# pickit4_adapter.net
KiCad netlist of a schematic drawn in EAGLE
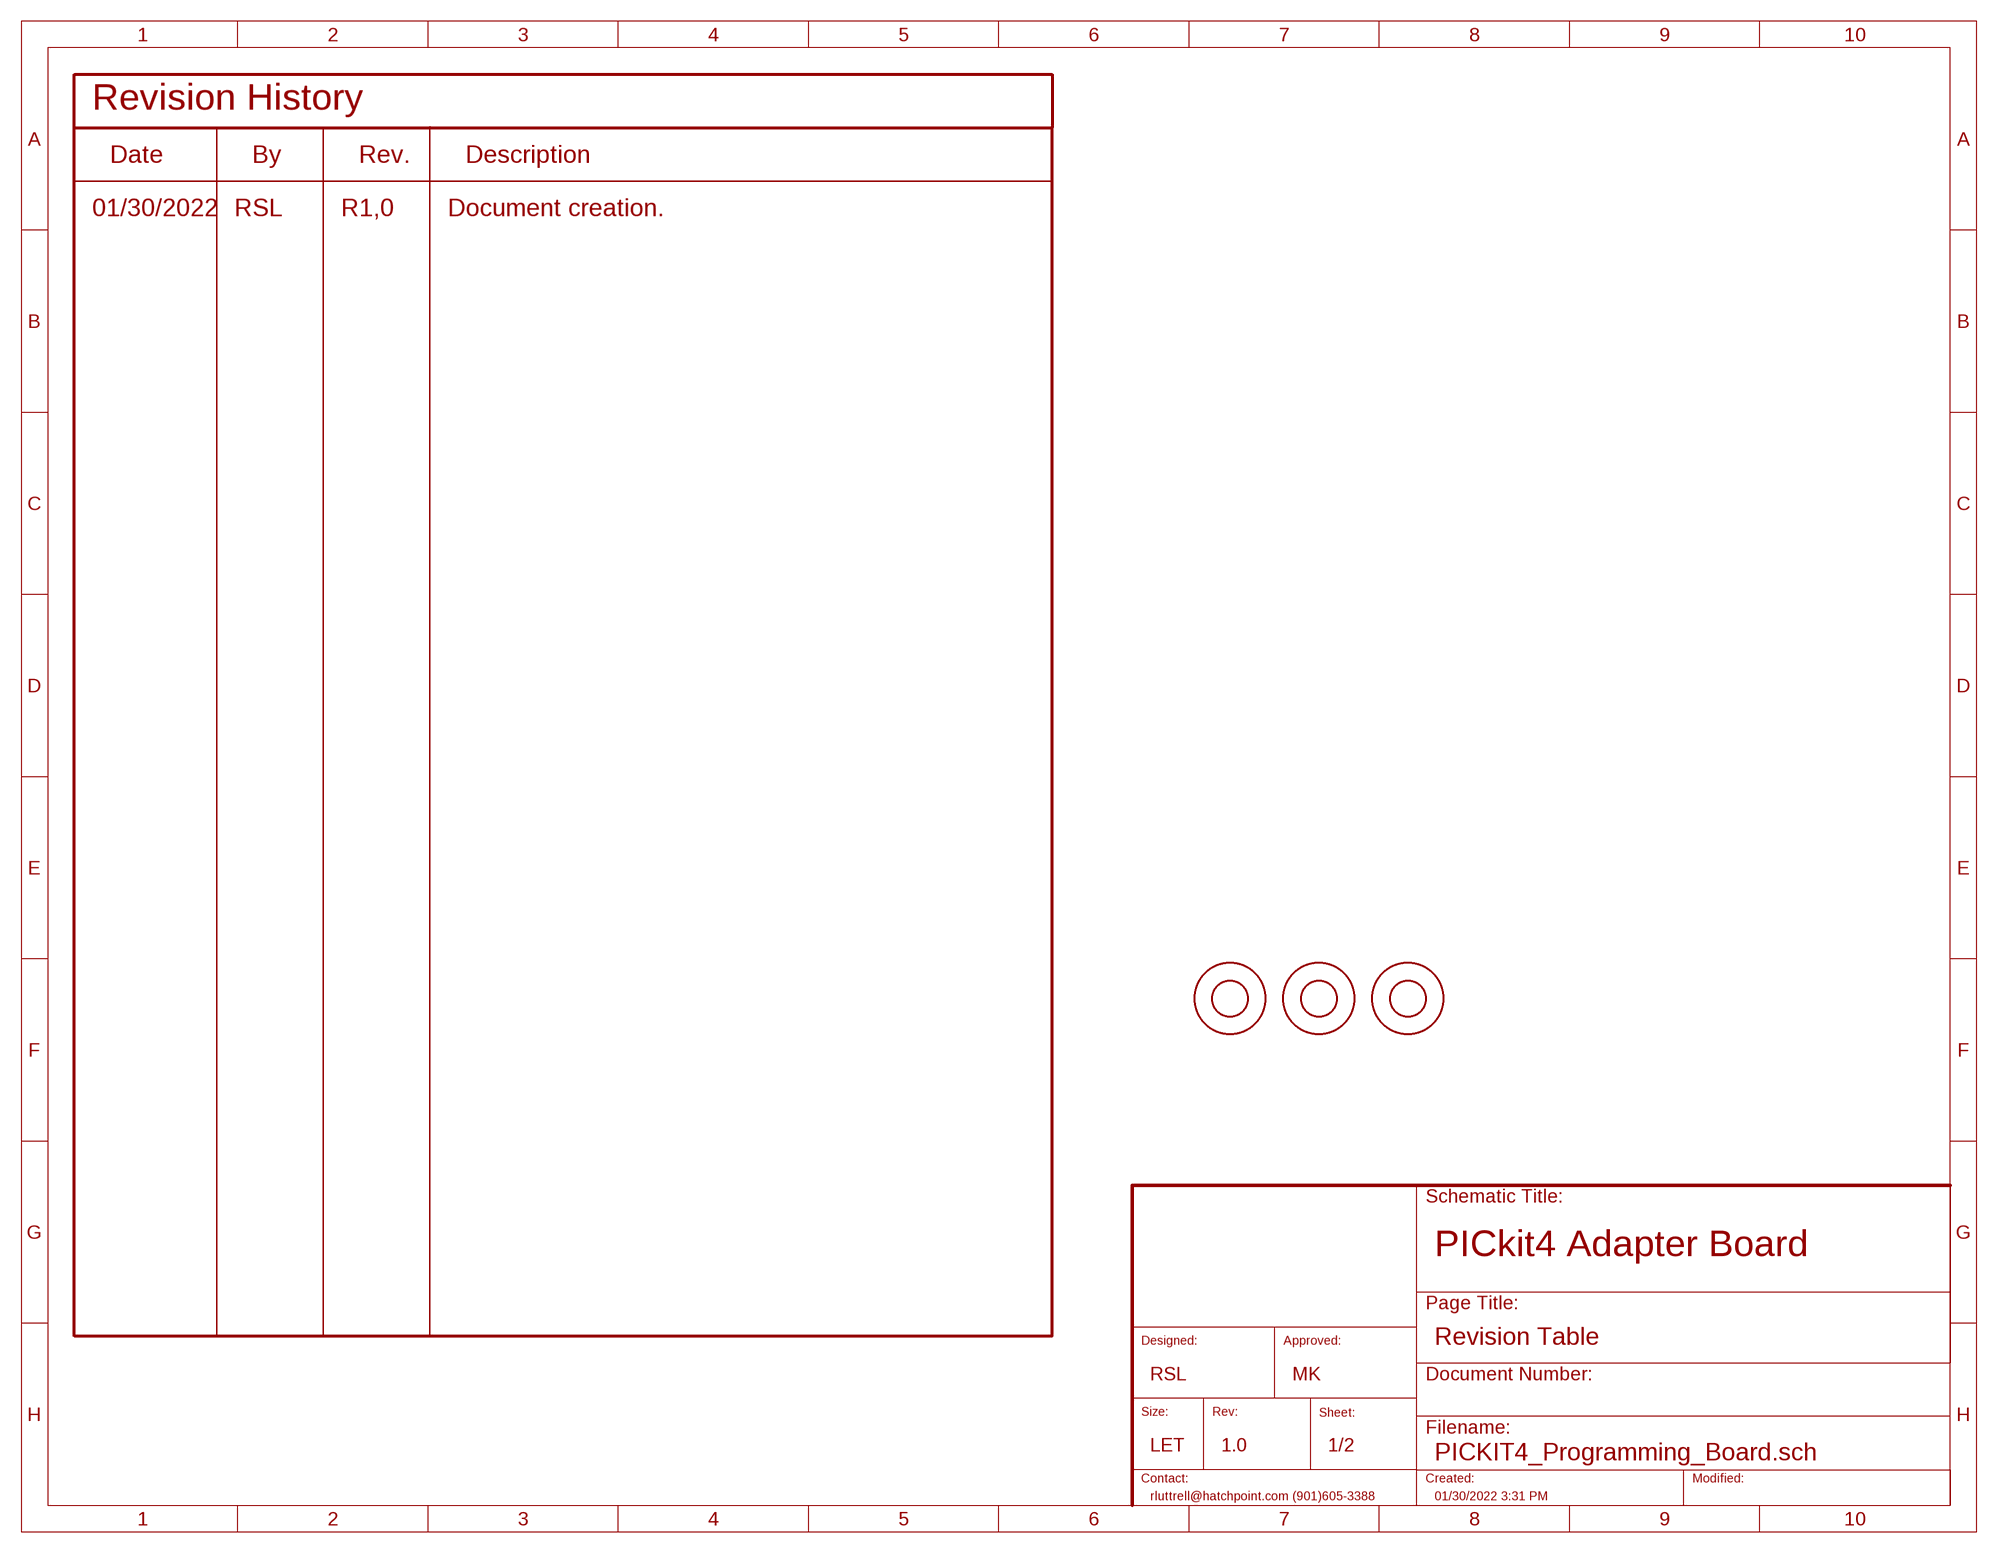
[diagram p0: schematic, sheet 1]
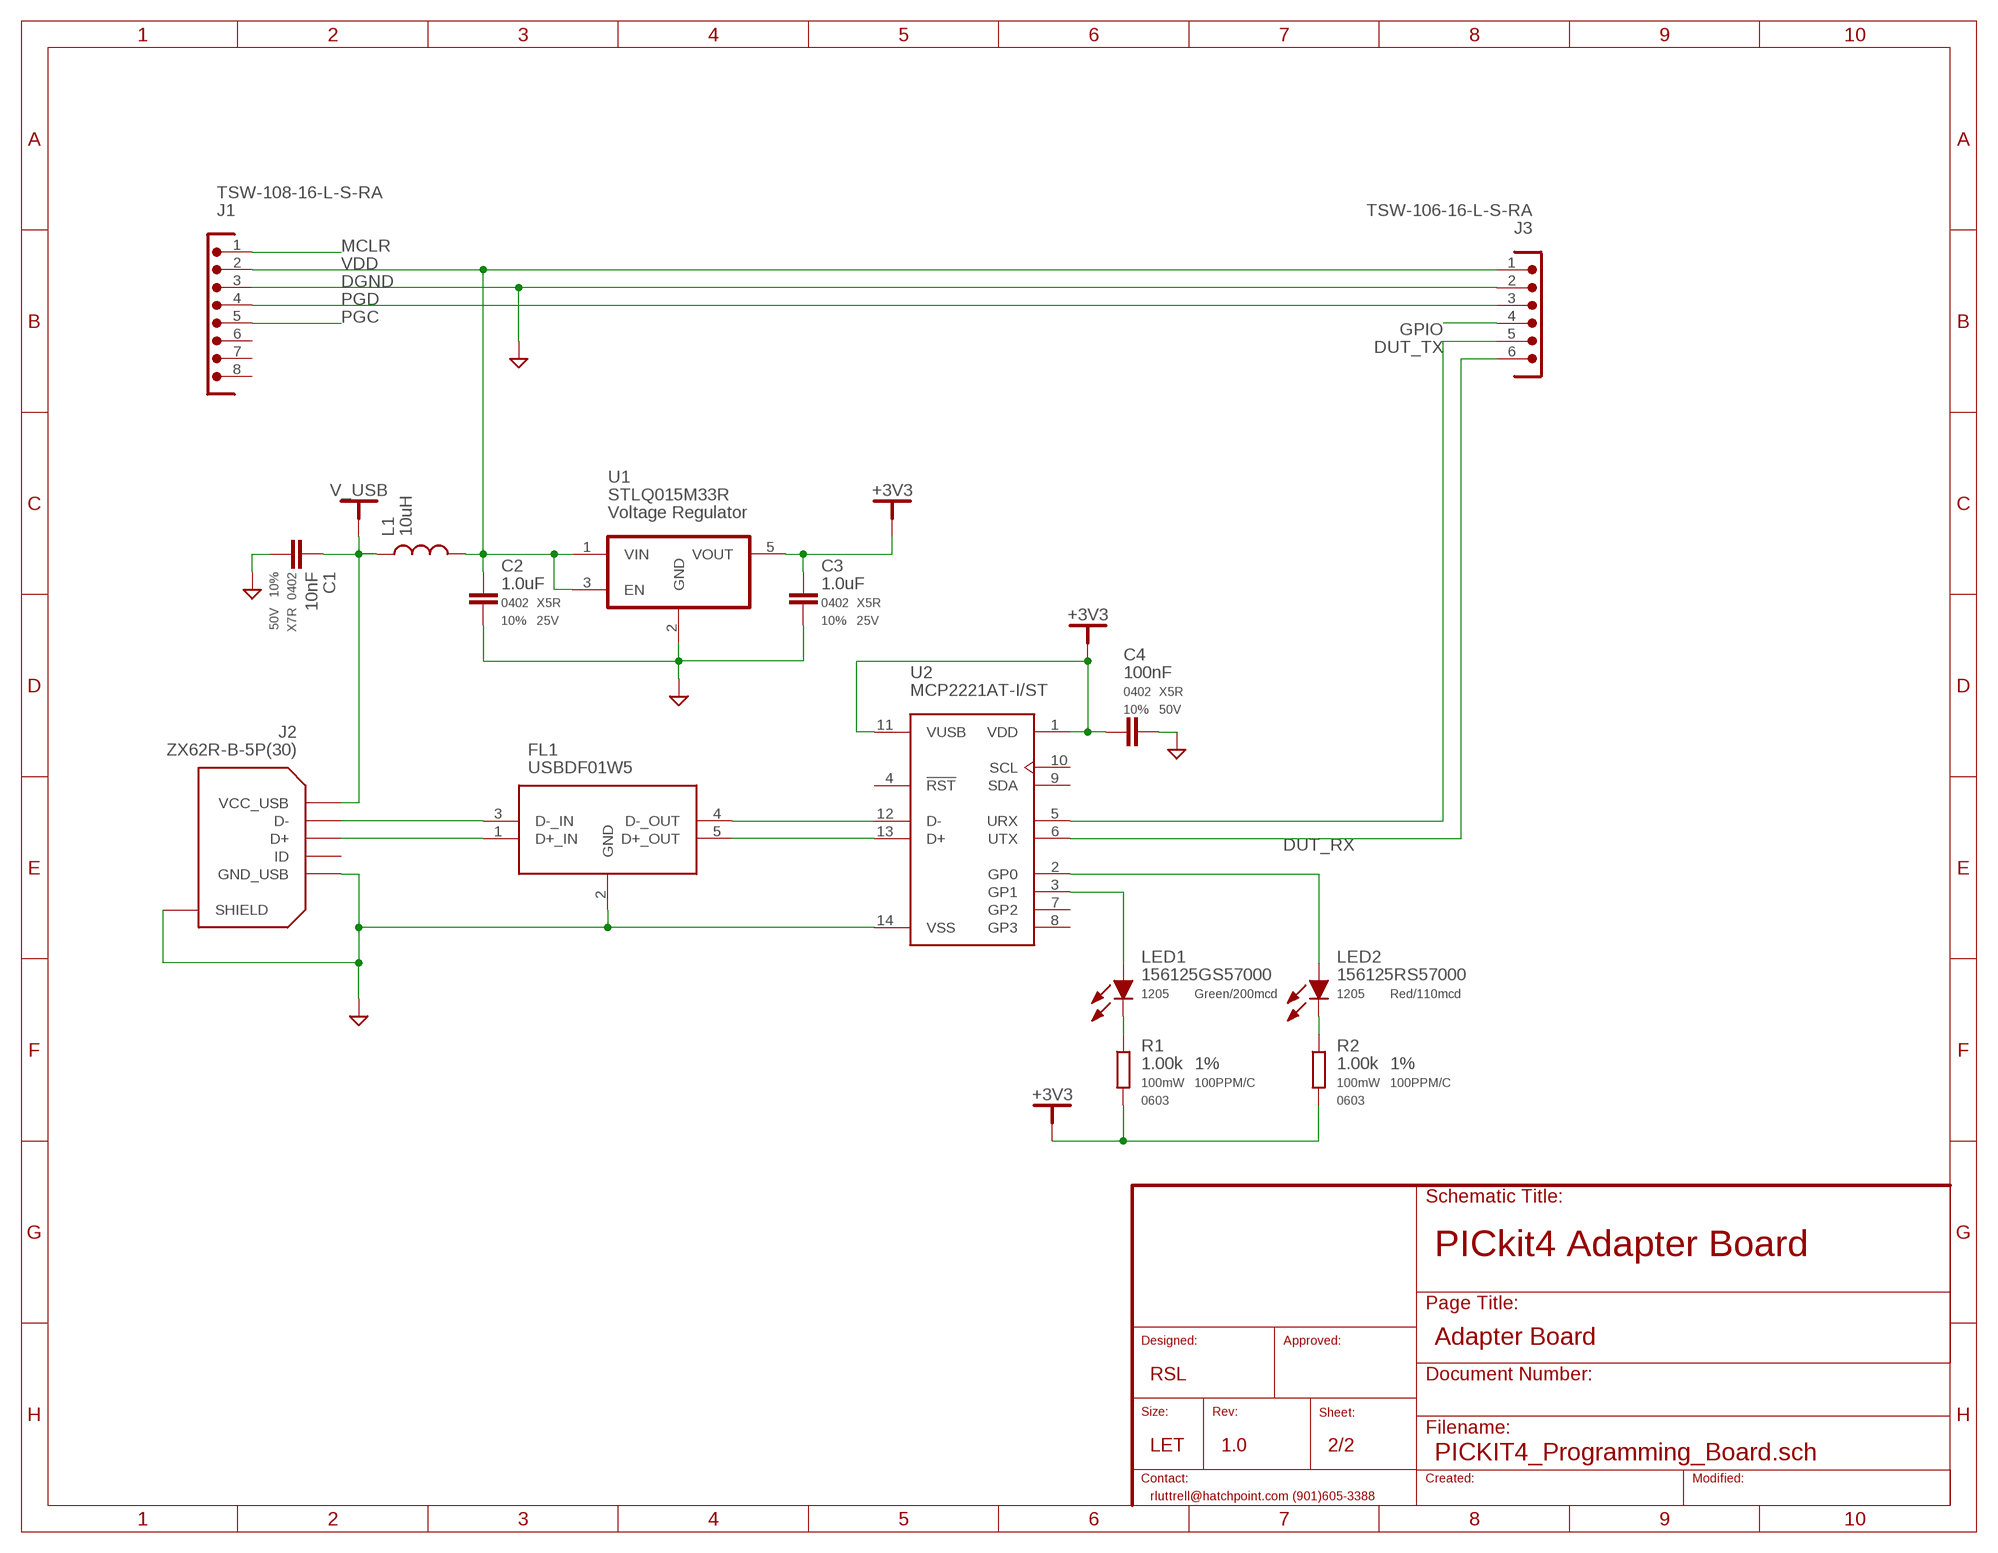
[diagram p1: schematic, sheet 2]

(export (version "E")
  (design (tool "Eeschema 10.0.6"))
  (components
    (comp (ref "C1")
      (value "10nF")
      (footprint "eagle-import:CAPC_0402_1005X55N")
      (fields
        (field (name "MANUFACTURER") "Murata")
        (field (name "PACKAGE") "0402")
        (field (name "TOL") "10%")
        (field (name "TYPE") "X7R")
        (field (name "VDC") "50V")
      )
      (libsource (lib "eagle-import") (part "GRM?155R71H103KA88D"))
    )
    (comp (ref "C2")
      (value "1.0uF")
      (footprint "eagle-import:CAPC_0402_1005X55N")
      (fields
        (field (name "MANUFACTURER") "Murata")
        (field (name "PACKAGE") "0402")
        (field (name "TOL") "10%")
        (field (name "TYPE") "X5R")
        (field (name "VDC") "25V")
      )
      (libsource (lib "eagle-import") (part "GRM?155R61E105KA12D"))
    )
    (comp (ref "C3")
      (value "1.0uF")
      (footprint "eagle-import:CAPC_0402_1005X55N")
      (fields
        (field (name "MANUFACTURER") "Murata")
        (field (name "PACKAGE") "0402")
        (field (name "TOL") "10%")
        (field (name "TYPE") "X5R")
        (field (name "VDC") "25V")
      )
      (libsource (lib "eagle-import") (part "GRM?155R61E105KA12D"))
    )
    (comp (ref "C4")
      (value "100nF")
      (footprint "eagle-import:CAPC_0402_1005X55N")
      (fields
        (field (name "MANUFACTURER") "Murata")
        (field (name "PACKAGE") "0402")
        (field (name "TOL") "10%")
        (field (name "TYPE") "X5R")
        (field (name "VDC") "50V")
      )
      (libsource (lib "eagle-import") (part "GRM?155R61H104KE19D"))
    )
    (comp (ref "FL1")
      (value "USBDF01W5")
      (footprint "eagle-import:SOT65P210X110-5N")
      (fields (field (name "MANUFACTURER") "ST"))
      (libsource (lib "eagle-import") (part "USBDF0W51"))
    )
    (comp (ref "J1")
      (value "TSW-108-16-L-S-RA")
      (footprint "eagle-import:HDR-100MIL-1X8-THRU-RA")
      (libsource (lib "eagle-import") (part "TSW-108-16-L-S-RA"))
    )
    (comp (ref "J2")
      (value "ZX62R-B-5P(30)")
      (footprint "eagle-import:ZX62R-B-5P(30)")
      (libsource (lib "eagle-import") (part "ZX62?R-B-5P(30)"))
    )
    (comp (ref "J3")
      (value "TSW-106-16-L-S-RA")
      (footprint "eagle-import:HDR-100MIL-1X6-THRU-RA")
      (libsource (lib "eagle-import") (part "TSW-106-16-L-S-RA"))
    )
    (comp (ref "L1")
      (value "10uH")
      (footprint "eagle-import:INDC1608X90N")
      (fields (field (name "MF") "Taiyo Yuden") (field (name "MP") "LB1608T100M"))
      (libsource (lib "eagle-import") (part "LB1608T100M"))
    )
    (comp (ref "LED1")
      (value "156125GS57000")
      (footprint "eagle-import:LEDC3212X120N")
      (fields (field (name "PACKAGE") "1205"))
      (libsource (lib "eagle-import") (part "15612557000GS"))
    )
    (comp (ref "LED2")
      (value "156125RS57000")
      (footprint "eagle-import:LEDC3212X120N")
      (fields (field (name "PACKAGE") "1205"))
      (libsource (lib "eagle-import") (part "15612557000RS"))
    )
    (comp (ref "R1")
      (value "1.00k")
      (footprint "eagle-import:R0603K")
      (fields
        (field (name "MF") "Vishay")
        (field (name "PACKAGE") "0603")
        (field (name "PWR_RATE") "100mW")
        (field (name "TEMPCO") "100PPM/C")
        (field (name "TOLERANCE") "1%")
      )
      (libsource (lib "eagle-import") (part "CRCW?06031K00FKEAC"))
    )
    (comp (ref "R2")
      (value "1.00k")
      (footprint "eagle-import:R0603K")
      (fields
        (field (name "MF") "Vishay")
        (field (name "PACKAGE") "0603")
        (field (name "PWR_RATE") "100mW")
        (field (name "TEMPCO") "100PPM/C")
        (field (name "TOLERANCE") "1%")
      )
      (libsource (lib "eagle-import") (part "CRCW?06031K00FKEAC"))
    )
    (comp (ref "U1")
      (value "STLQ015M33R")
      (footprint "eagle-import:SOT23-5L")
      (fields
        (field (name "DESC") "Voltage Regulator")
        (field (name "MF") "STM")
        (field (name "VOLTAGE") "3.3V")
      )
      (libsource (lib "eagle-import") (part "STLQ015MR33"))
    )
    (comp (ref "U2")
      (value "MCP2221AT-I/ST")
      (footprint "eagle-import:SOP65P640X120-14N")
      (fields
        (field (name "ARROW_PART_NUMBER") "MCP2221A-I/ST")
        (field (name "MOUSER_PART_NUMBER") "579-MCP2221A-I/ST")
      )
      (libsource (lib "eagle-import") (part "MCP2221AT-I/ST"))
    )
    (comp (ref "FID1")
      (value "FIDUCIAL_1MM_TOP_BOTTOM")
      (footprint "eagle-import:FIDUCIAL_1MM_TOP_BOTTOM")
      (libsource (lib "eagle-import") (part "FIDUCIAL_1MM_TOP_BOTTOM"))
    )
    (comp (ref "FID2")
      (value "FIDUCIAL_1MM_TOP_BOTTOM")
      (footprint "eagle-import:FIDUCIAL_1MM_TOP_BOTTOM")
      (libsource (lib "eagle-import") (part "FIDUCIAL_1MM_TOP_BOTTOM"))
    )
    (comp (ref "FID3")
      (value "FIDUCIAL_1MM_TOP_BOTTOM")
      (footprint "eagle-import:FIDUCIAL_1MM_TOP_BOTTOM")
      (libsource (lib "eagle-import") (part "FIDUCIAL_1MM_TOP_BOTTOM"))
    )
  )
  (nets
    (net (code "1") (name "+3V3") (class "Default")
      (node (ref "C3") (pin "1") (pinfunction "1_1") (pintype "passive"))
      (node (ref "C4") (pin "1") (pinfunction "1_1") (pintype "passive"))
      (node (ref "R1") (pin "2") (pinfunction "2_2") (pintype "passive"))
      (node (ref "R2") (pin "2") (pinfunction "2_2") (pintype "passive"))
      (node (ref "U1") (pin "5") (pinfunction "VOUT_5") (pintype "power_in"))
      (node (ref "U2") (pin "1") (pinfunction "VDD_1") (pintype "bidirectional"))
      (node (ref "U2") (pin "11") (pinfunction "VUSB_11") (pintype "bidirectional"))
    )
    (net (code "2") (name "DGND") (class "Default")
      (node (ref "C1") (pin "2") (pinfunction "2_2") (pintype "passive"))
      (node (ref "C2") (pin "2") (pinfunction "2_2") (pintype "passive"))
      (node (ref "C3") (pin "2") (pinfunction "2_2") (pintype "passive"))
      (node (ref "C4") (pin "2") (pinfunction "2_2") (pintype "passive"))
      (node (ref "FL1") (pin "2") (pinfunction "GND_2") (pintype "power_in"))
      (node (ref "J1") (pin "3") (pinfunction "3_3") (pintype "passive"))
      (node (ref "J2") (pin "10") (pinfunction "SHIELD_10") (pintype "bidirectional"))
      (node (ref "J2") (pin "11") (pinfunction "SHIELD_11") (pintype "bidirectional"))
      (node (ref "J2") (pin "5") (pinfunction "GND_USB_5") (pintype "bidirectional"))
      (node (ref "J2") (pin "6") (pinfunction "SHIELD_6") (pintype "bidirectional"))
      (node (ref "J2") (pin "7") (pinfunction "SHIELD_7") (pintype "bidirectional"))
      (node (ref "J2") (pin "8") (pinfunction "SHIELD_8") (pintype "bidirectional"))
      (node (ref "J2") (pin "9") (pinfunction "SHIELD_9") (pintype "bidirectional"))
      (node (ref "J3") (pin "2") (pinfunction "2_2") (pintype "passive"))
      (node (ref "U1") (pin "2") (pinfunction "GND_2") (pintype "power_in"))
      (node (ref "U2") (pin "14") (pinfunction "VSS_14") (pintype "bidirectional"))
    )
    (net (code "3") (name "DUT_RX") (class "Default")
      (node (ref "J3") (pin "6") (pinfunction "6_6") (pintype "passive"))
      (node (ref "U2") (pin "6") (pinfunction "UTX_6") (pintype "bidirectional"))
    )
    (net (code "4") (name "DUT_TX") (class "Default")
      (node (ref "J3") (pin "5") (pinfunction "5_5") (pintype "passive"))
      (node (ref "U2") (pin "5") (pinfunction "URX_5") (pintype "bidirectional"))
    )
    (net (code "5") (name "GPIO") (class "Default")
      (node (ref "J3") (pin "4") (pinfunction "4_4") (pintype "passive"))
    )
    (net (code "6") (name "MCLR") (class "Default")
      (node (ref "J1") (pin "1") (pinfunction "1_1") (pintype "passive"))
    )
    (net (code "7") (name "Net-(FL1-D+_IN)") (class "Default")
      (node (ref "FL1") (pin "1") (pinfunction "D+_IN_1") (pintype "input"))
      (node (ref "J2") (pin "3") (pinfunction "D+_3") (pintype "bidirectional"))
    )
    (net (code "8") (name "Net-(FL1-D+_OUT)") (class "Default")
      (node (ref "FL1") (pin "5") (pinfunction "D+_OUT_5") (pintype "output"))
      (node (ref "U2") (pin "13") (pinfunction "D+_13") (pintype "bidirectional"))
    )
    (net (code "9") (name "Net-(FL1-D-_IN)") (class "Default")
      (node (ref "FL1") (pin "3") (pinfunction "D-_IN_3") (pintype "input"))
      (node (ref "J2") (pin "2") (pinfunction "D-_2") (pintype "bidirectional"))
    )
    (net (code "10") (name "Net-(FL1-D-_OUT)") (class "Default")
      (node (ref "FL1") (pin "4") (pinfunction "D-_OUT_4") (pintype "output"))
      (node (ref "U2") (pin "12") (pinfunction "D-_12") (pintype "bidirectional"))
    )
    (net (code "11") (name "Net-(LED1-A)") (class "Default")
      (node (ref "LED1") (pin "2") (pinfunction "A_2") (pintype "bidirectional"))
      (node (ref "U2") (pin "3") (pinfunction "GP1_3") (pintype "bidirectional"))
    )
    (net (code "12") (name "Net-(LED1-K)") (class "Default")
      (node (ref "LED1") (pin "1") (pinfunction "K_1") (pintype "bidirectional"))
      (node (ref "R1") (pin "1") (pinfunction "1_1") (pintype "passive"))
    )
    (net (code "13") (name "Net-(LED2-A)") (class "Default")
      (node (ref "LED2") (pin "2") (pinfunction "A_2") (pintype "bidirectional"))
      (node (ref "U2") (pin "2") (pinfunction "GP0_2") (pintype "bidirectional"))
    )
    (net (code "14") (name "Net-(LED2-K)") (class "Default")
      (node (ref "LED2") (pin "1") (pinfunction "K_1") (pintype "bidirectional"))
      (node (ref "R2") (pin "1") (pinfunction "1_1") (pintype "passive"))
    )
    (net (code "15") (name "PGC") (class "Default")
      (node (ref "J1") (pin "5") (pinfunction "5_5") (pintype "passive"))
    )
    (net (code "16") (name "PGD") (class "Default")
      (node (ref "J1") (pin "4") (pinfunction "4_4") (pintype "passive"))
      (node (ref "J3") (pin "3") (pinfunction "3_3") (pintype "passive"))
    )
    (net (code "17") (name "VDD") (class "Default")
      (node (ref "C2") (pin "1") (pinfunction "1_1") (pintype "passive"))
      (node (ref "J1") (pin "2") (pinfunction "2_2") (pintype "passive"))
      (node (ref "J3") (pin "1") (pinfunction "1_1") (pintype "passive"))
      (node (ref "L1") (pin "2") (pinfunction "2_2") (pintype "passive"))
      (node (ref "U1") (pin "1") (pinfunction "VIN_1") (pintype "power_in"))
      (node (ref "U1") (pin "3") (pinfunction "EN_3") (pintype "input"))
    )
    (net (code "18") (name "V_USB") (class "Default")
      (node (ref "C1") (pin "1") (pinfunction "1_1") (pintype "passive"))
      (node (ref "J2") (pin "1") (pinfunction "VCC_USB_1") (pintype "bidirectional"))
      (node (ref "L1") (pin "1") (pinfunction "1_1") (pintype "passive"))
    )
    (net (code "19") (name "unconnected-(J1-Pad6)") (class "Default")
      (node (ref "J1") (pin "6") (pinfunction "6_6") (pintype "passive"))
    )
    (net (code "20") (name "unconnected-(J1-Pad7)") (class "Default")
      (node (ref "J1") (pin "7") (pinfunction "7_7") (pintype "passive"))
    )
    (net (code "21") (name "unconnected-(J1-Pad8)") (class "Default")
      (node (ref "J1") (pin "8") (pinfunction "8_8") (pintype "passive"))
    )
    (net (code "22") (name "unconnected-(J2-ID-Pad4)") (class "Default")
      (node (ref "J2") (pin "4") (pinfunction "ID_4") (pintype "bidirectional"))
    )
    (net (code "23") (name "unconnected-(U2-GP2-Pad7)") (class "Default")
      (node (ref "U2") (pin "7") (pinfunction "GP2_7") (pintype "bidirectional"))
    )
    (net (code "24") (name "unconnected-(U2-GP3-Pad8)") (class "Default")
      (node (ref "U2") (pin "8") (pinfunction "GP3_8") (pintype "bidirectional"))
    )
    (net (code "25") (name "unconnected-(U2-SCL-Pad10)") (class "Default")
      (node (ref "U2") (pin "10") (pinfunction "SCL_10") (pintype "bidirectional"))
    )
    (net (code "26") (name "unconnected-(U2-SDA-Pad9)") (class "Default")
      (node (ref "U2") (pin "9") (pinfunction "SDA_9") (pintype "bidirectional"))
    )
    (net (code "27") (name "unconnected-(U2-~{RST}-Pad4)") (class "Default")
      (node (ref "U2") (pin "4") (pinfunction "~{RST}_4") (pintype "bidirectional"))
    )
  )
)
